# Power_Input_Board.net
KiCad netlist of a schematic drawn in EAGLE
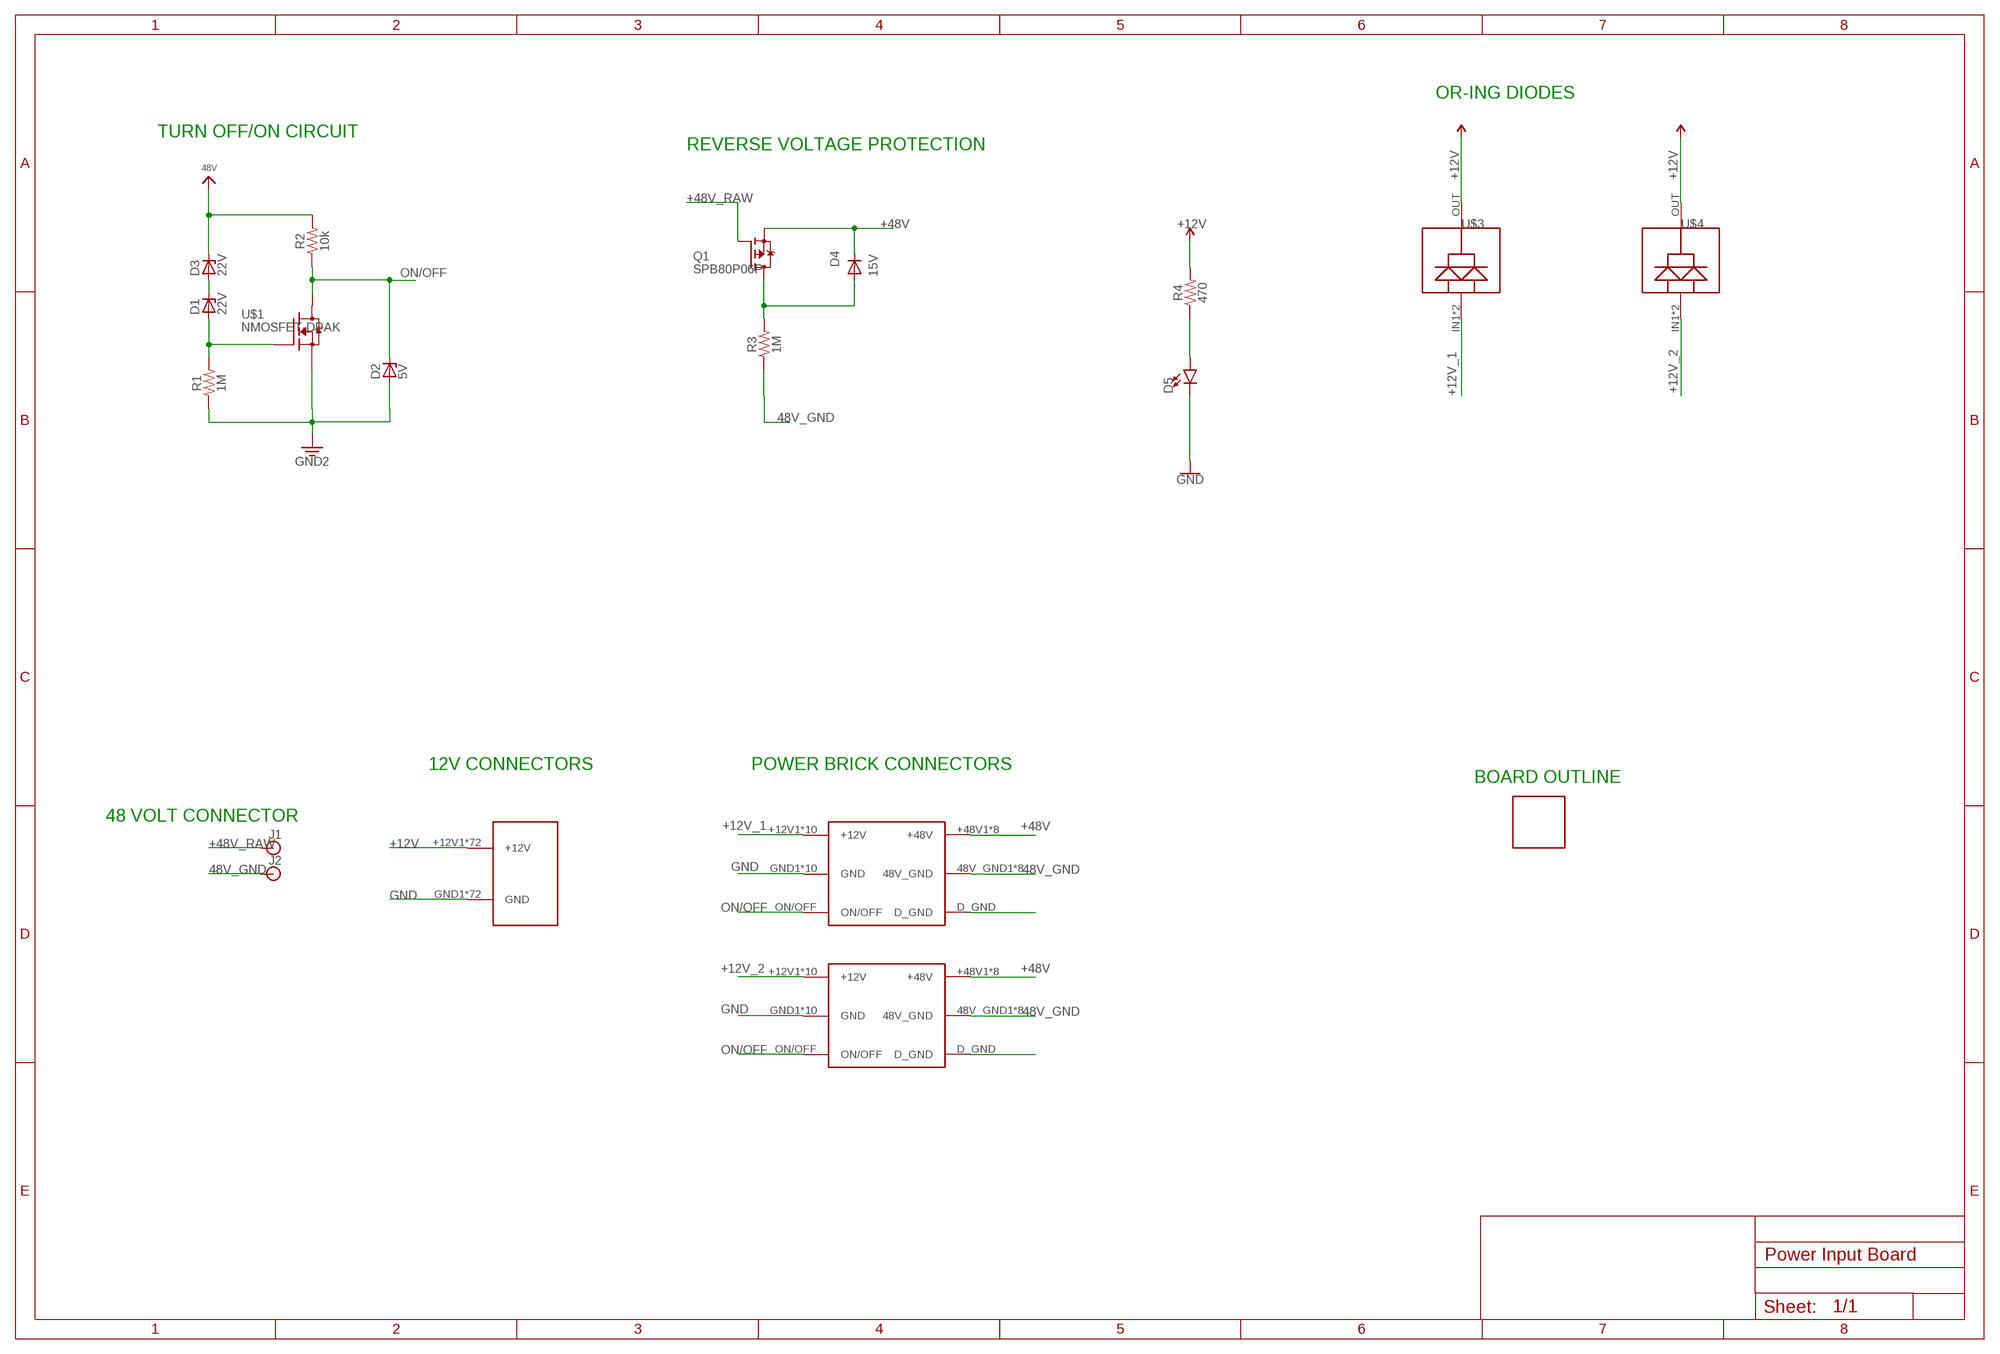
[diagram p0: schematic, sheet 1]

(export (version "E")
  (design (tool "Eeschema 10.0.6"))
  (components
    (comp (ref "D1")
      (value "22V")
      (footprint "eagle-import:SOT23")
      (libsource (lib "eagle-import") (part "ZENER-DIODESOT23"))
    )
    (comp (ref "D2")
      (value "5V")
      (footprint "eagle-import:SOT23")
      (libsource (lib "eagle-import") (part "ZENER-DIODESOT23"))
    )
    (comp (ref "D3")
      (value "22V")
      (footprint "eagle-import:SOT23")
      (libsource (lib "eagle-import") (part "ZENER-DIODESOT23"))
    )
    (comp (ref "D4")
      (value "15V")
      (footprint "eagle-import:SOD123")
      (libsource (lib "eagle-import") (part "DIODE-SOD123"))
    )
    (comp (ref "D5")
      (value "LED0603")
      (footprint "eagle-import:LED-0603")
      (libsource (lib "eagle-import") (part "LED0603"))
    )
    (comp (ref "J1")
      (value "BANANA_CONN")
      (footprint "eagle-import:BANANA_CONN")
      (libsource (lib "eagle-import") (part "BANANA_CONN"))
    )
    (comp (ref "J2")
      (value "BANANA_CONN")
      (footprint "eagle-import:BANANA_CONN")
      (libsource (lib "eagle-import") (part "BANANA_CONN"))
    )
    (comp (ref "Q1")
      (value "SPB80P06P")
      (footprint "eagle-import:TO263")
      (libsource (lib "eagle-import") (part "SPB80P06P"))
    )
    (comp (ref "R1")
      (value "1M")
      (footprint "eagle-import:0603")
      (fields (field (name "SPICEPREFIX") "R"))
      (libsource (lib "eagle-import") (part "RESISTOR0603"))
    )
    (comp (ref "R2")
      (value "10k")
      (footprint "eagle-import:0603")
      (fields (field (name "SPICEPREFIX") "R"))
      (libsource (lib "eagle-import") (part "RESISTOR0603"))
    )
    (comp (ref "R3")
      (value "1M")
      (footprint "eagle-import:0603")
      (fields (field (name "SPICEPREFIX") "R"))
      (libsource (lib "eagle-import") (part "RESISTOR0603"))
    )
    (comp (ref "R4")
      (value "470")
      (footprint "eagle-import:0603")
      (libsource (lib "eagle-import") (part "RESISTOR0603"))
    )
    (comp (ref "U$1")
      (value "NMOSFET-DPAK")
      (footprint "eagle-import:DPAK")
      (libsource (lib "eagle-import") (part "NMOSFET-DPAK"))
    )
    (comp (ref "U$2")
      (value "BOARDPDB")
      (footprint "eagle-import:PDB")
      (libsource (lib "eagle-import") (part "BOARDPDB"))
    )
    (comp (ref "U$3")
      (value "DIODE")
      (footprint "eagle-import:DIODE")
      (libsource (lib "eagle-import") (part "DIODE"))
    )
    (comp (ref "U$4")
      (value "DIODE")
      (footprint "eagle-import:DIODE")
      (libsource (lib "eagle-import") (part "DIODE"))
    )
    (comp (ref "U$5")
      (value "BRICK_TO_POWER_DIST_WHOLE")
      (footprint "eagle-import:BRICK_TO_POWER_DIST_WHOLE")
      (libsource (lib "eagle-import") (part "BRICK_TO_POWER_DIST_WHOLE"))
    )
    (comp (ref "U$6")
      (value "BRICK_TO_POWER_DIST_WHOLE")
      (footprint "eagle-import:BRICK_TO_POWER_DIST_WHOLE")
      (libsource (lib "eagle-import") (part "BRICK_TO_POWER_DIST_WHOLE"))
    )
    (comp (ref "U$7")
      (value "PDB_PCB_CONNEC")
      (footprint "eagle-import:PDB_PCB_2")
      (libsource (lib "eagle-import") (part "PDB_PCB_CONNEC"))
    )
  )
  (nets
    (net (code "1") (name "/+12V_1") (class "Default")
      (node (ref "U$3") (pin "IN1") (pinfunction "IN2_IN1") (pintype "bidirectional"))
      (node (ref "U$3") (pin "IN2") (pinfunction "IN2_IN2") (pintype "bidirectional"))
      (node (ref "U$5") (pin "+12V1") (pinfunction "+12V_+12V1") (pintype "bidirectional"))
      (node (ref "U$5") (pin "+12V10") (pinfunction "+12V_+12V10") (pintype "bidirectional"))
      (node (ref "U$5") (pin "+12V2") (pinfunction "+12V_+12V2") (pintype "bidirectional"))
      (node (ref "U$5") (pin "+12V3") (pinfunction "+12V_+12V3") (pintype "bidirectional"))
      (node (ref "U$5") (pin "+12V4") (pinfunction "+12V_+12V4") (pintype "bidirectional"))
      (node (ref "U$5") (pin "+12V5") (pinfunction "+12V_+12V5") (pintype "bidirectional"))
      (node (ref "U$5") (pin "+12V6") (pinfunction "+12V_+12V6") (pintype "bidirectional"))
      (node (ref "U$5") (pin "+12V7") (pinfunction "+12V_+12V7") (pintype "bidirectional"))
      (node (ref "U$5") (pin "+12V8") (pinfunction "+12V_+12V8") (pintype "bidirectional"))
      (node (ref "U$5") (pin "+12V9") (pinfunction "+12V_+12V9") (pintype "bidirectional"))
    )
    (net (code "2") (name "/+12V_2") (class "Default")
      (node (ref "U$4") (pin "IN1") (pinfunction "IN2_IN1") (pintype "bidirectional"))
      (node (ref "U$4") (pin "IN2") (pinfunction "IN2_IN2") (pintype "bidirectional"))
      (node (ref "U$6") (pin "+12V1") (pinfunction "+12V_+12V1") (pintype "bidirectional"))
      (node (ref "U$6") (pin "+12V10") (pinfunction "+12V_+12V10") (pintype "bidirectional"))
      (node (ref "U$6") (pin "+12V2") (pinfunction "+12V_+12V2") (pintype "bidirectional"))
      (node (ref "U$6") (pin "+12V3") (pinfunction "+12V_+12V3") (pintype "bidirectional"))
      (node (ref "U$6") (pin "+12V4") (pinfunction "+12V_+12V4") (pintype "bidirectional"))
      (node (ref "U$6") (pin "+12V5") (pinfunction "+12V_+12V5") (pintype "bidirectional"))
      (node (ref "U$6") (pin "+12V6") (pinfunction "+12V_+12V6") (pintype "bidirectional"))
      (node (ref "U$6") (pin "+12V7") (pinfunction "+12V_+12V7") (pintype "bidirectional"))
      (node (ref "U$6") (pin "+12V8") (pinfunction "+12V_+12V8") (pintype "bidirectional"))
      (node (ref "U$6") (pin "+12V9") (pinfunction "+12V_+12V9") (pintype "bidirectional"))
    )
    (net (code "3") (name "/+48V") (class "Default")
      (node (ref "D4") (pin "C") (pinfunction "C_C") (pintype "passive"))
      (node (ref "Q1") (pin "2") (pinfunction "S_2") (pintype "passive"))
      (node (ref "U$5") (pin "+48V1") (pinfunction "+48V_+48V1") (pintype "bidirectional"))
      (node (ref "U$5") (pin "+48V2") (pinfunction "+48V_+48V2") (pintype "bidirectional"))
      (node (ref "U$5") (pin "+48V3") (pinfunction "+48V_+48V3") (pintype "bidirectional"))
      (node (ref "U$5") (pin "+48V4") (pinfunction "+48V_+48V4") (pintype "bidirectional"))
      (node (ref "U$5") (pin "+48V5") (pinfunction "+48V_+48V5") (pintype "bidirectional"))
      (node (ref "U$5") (pin "+48V6") (pinfunction "+48V_+48V6") (pintype "bidirectional"))
      (node (ref "U$5") (pin "+48V7") (pinfunction "+48V_+48V7") (pintype "bidirectional"))
      (node (ref "U$5") (pin "+48V8") (pinfunction "+48V_+48V8") (pintype "bidirectional"))
      (node (ref "U$6") (pin "+48V1") (pinfunction "+48V_+48V1") (pintype "bidirectional"))
      (node (ref "U$6") (pin "+48V2") (pinfunction "+48V_+48V2") (pintype "bidirectional"))
      (node (ref "U$6") (pin "+48V3") (pinfunction "+48V_+48V3") (pintype "bidirectional"))
      (node (ref "U$6") (pin "+48V4") (pinfunction "+48V_+48V4") (pintype "bidirectional"))
      (node (ref "U$6") (pin "+48V5") (pinfunction "+48V_+48V5") (pintype "bidirectional"))
      (node (ref "U$6") (pin "+48V6") (pinfunction "+48V_+48V6") (pintype "bidirectional"))
      (node (ref "U$6") (pin "+48V7") (pinfunction "+48V_+48V7") (pintype "bidirectional"))
      (node (ref "U$6") (pin "+48V8") (pinfunction "+48V_+48V8") (pintype "bidirectional"))
    )
    (net (code "4") (name "/+48V_RAW") (class "Default")
      (node (ref "J1") (pin "P$1") (pinfunction "1_P$1") (pintype "passive"))
      (node (ref "Q1") (pin "1") (pinfunction "G_1") (pintype "passive"))
    )
    (net (code "5") (name "/48V_GND") (class "Default")
      (node (ref "J2") (pin "P$1") (pinfunction "1_P$1") (pintype "passive"))
      (node (ref "R3") (pin "1") (pinfunction "1_1") (pintype "passive"))
      (node (ref "U$5") (pin "48V_GND1") (pinfunction "48V_GND_48V_GND1") (pintype "bidirectional"))
      (node (ref "U$5") (pin "48V_GND2") (pinfunction "48V_GND_48V_GND2") (pintype "bidirectional"))
      (node (ref "U$5") (pin "48V_GND3") (pinfunction "48V_GND_48V_GND3") (pintype "bidirectional"))
      (node (ref "U$5") (pin "48V_GND4") (pinfunction "48V_GND_48V_GND4") (pintype "bidirectional"))
      (node (ref "U$5") (pin "48V_GND5") (pinfunction "48V_GND_48V_GND5") (pintype "bidirectional"))
      (node (ref "U$5") (pin "48V_GND6") (pinfunction "48V_GND_48V_GND6") (pintype "bidirectional"))
      (node (ref "U$5") (pin "48V_GND7") (pinfunction "48V_GND_48V_GND7") (pintype "bidirectional"))
      (node (ref "U$5") (pin "48V_GND8") (pinfunction "48V_GND_48V_GND8") (pintype "bidirectional"))
      (node (ref "U$6") (pin "48V_GND1") (pinfunction "48V_GND_48V_GND1") (pintype "bidirectional"))
      (node (ref "U$6") (pin "48V_GND2") (pinfunction "48V_GND_48V_GND2") (pintype "bidirectional"))
      (node (ref "U$6") (pin "48V_GND3") (pinfunction "48V_GND_48V_GND3") (pintype "bidirectional"))
      (node (ref "U$6") (pin "48V_GND4") (pinfunction "48V_GND_48V_GND4") (pintype "bidirectional"))
      (node (ref "U$6") (pin "48V_GND5") (pinfunction "48V_GND_48V_GND5") (pintype "bidirectional"))
      (node (ref "U$6") (pin "48V_GND6") (pinfunction "48V_GND_48V_GND6") (pintype "bidirectional"))
      (node (ref "U$6") (pin "48V_GND7") (pinfunction "48V_GND_48V_GND7") (pintype "bidirectional"))
      (node (ref "U$6") (pin "48V_GND8") (pinfunction "48V_GND_48V_GND8") (pintype "bidirectional"))
    )
    (net (code "6") (name "/ON{slash}OFF") (class "Default")
      (node (ref "D2") (pin "3") (pinfunction "C_3") (pintype "passive"))
      (node (ref "R2") (pin "1") (pinfunction "1_1") (pintype "passive"))
      (node (ref "U$1") (pin "4") (pinfunction "D1_4") (pintype "passive"))
      (node (ref "U$5") (pin "ON/OFF") (pinfunction "ON/OFF_ON/OFF") (pintype "bidirectional"))
      (node (ref "U$6") (pin "ON/OFF") (pinfunction "ON/OFF_ON/OFF") (pintype "bidirectional"))
    )
    (net (code "7") (name "48V") (class "Default")
      (node (ref "D3") (pin "3") (pinfunction "C_3") (pintype "passive"))
      (node (ref "R2") (pin "2") (pinfunction "2_2") (pintype "passive"))
    )
    (net (code "8") (name "GND") (class "Default")
      (node (ref "D5") (pin "C") (pinfunction "C_C") (pintype "passive"))
      (node (ref "U$5") (pin "GND1") (pinfunction "GND_GND1") (pintype "bidirectional"))
      (node (ref "U$5") (pin "GND10") (pinfunction "GND_GND10") (pintype "bidirectional"))
      (node (ref "U$5") (pin "GND2") (pinfunction "GND_GND2") (pintype "bidirectional"))
      (node (ref "U$5") (pin "GND3") (pinfunction "GND_GND3") (pintype "bidirectional"))
      (node (ref "U$5") (pin "GND4") (pinfunction "GND_GND4") (pintype "bidirectional"))
      (node (ref "U$5") (pin "GND5") (pinfunction "GND_GND5") (pintype "bidirectional"))
      (node (ref "U$5") (pin "GND6") (pinfunction "GND_GND6") (pintype "bidirectional"))
      (node (ref "U$5") (pin "GND7") (pinfunction "GND_GND7") (pintype "bidirectional"))
      (node (ref "U$5") (pin "GND8") (pinfunction "GND_GND8") (pintype "bidirectional"))
      (node (ref "U$5") (pin "GND9") (pinfunction "GND_GND9") (pintype "bidirectional"))
      (node (ref "U$6") (pin "GND1") (pinfunction "GND_GND1") (pintype "bidirectional"))
      (node (ref "U$6") (pin "GND10") (pinfunction "GND_GND10") (pintype "bidirectional"))
      (node (ref "U$6") (pin "GND2") (pinfunction "GND_GND2") (pintype "bidirectional"))
      (node (ref "U$6") (pin "GND3") (pinfunction "GND_GND3") (pintype "bidirectional"))
      (node (ref "U$6") (pin "GND4") (pinfunction "GND_GND4") (pintype "bidirectional"))
      (node (ref "U$6") (pin "GND5") (pinfunction "GND_GND5") (pintype "bidirectional"))
      (node (ref "U$6") (pin "GND6") (pinfunction "GND_GND6") (pintype "bidirectional"))
      (node (ref "U$6") (pin "GND7") (pinfunction "GND_GND7") (pintype "bidirectional"))
      (node (ref "U$6") (pin "GND8") (pinfunction "GND_GND8") (pintype "bidirectional"))
      (node (ref "U$6") (pin "GND9") (pinfunction "GND_GND9") (pintype "bidirectional"))
      (node (ref "U$7") (pin "GND1") (pinfunction "GND_GND1") (pintype "bidirectional"))
      (node (ref "U$7") (pin "GND10") (pinfunction "GND_GND10") (pintype "bidirectional"))
      (node (ref "U$7") (pin "GND11") (pinfunction "GND_GND11") (pintype "bidirectional"))
      (node (ref "U$7") (pin "GND12") (pinfunction "GND_GND12") (pintype "bidirectional"))
      (node (ref "U$7") (pin "GND13") (pinfunction "GND_GND13") (pintype "bidirectional"))
      (node (ref "U$7") (pin "GND14") (pinfunction "GND_GND14") (pintype "bidirectional"))
      (node (ref "U$7") (pin "GND15") (pinfunction "GND_GND15") (pintype "bidirectional"))
      (node (ref "U$7") (pin "GND16") (pinfunction "GND_GND16") (pintype "bidirectional"))
      (node (ref "U$7") (pin "GND17") (pinfunction "GND_GND17") (pintype "bidirectional"))
      (node (ref "U$7") (pin "GND18") (pinfunction "GND_GND18") (pintype "bidirectional"))
      (node (ref "U$7") (pin "GND19") (pinfunction "GND_GND19") (pintype "bidirectional"))
      (node (ref "U$7") (pin "GND2") (pinfunction "GND_GND2") (pintype "bidirectional"))
      (node (ref "U$7") (pin "GND20") (pinfunction "GND_GND20") (pintype "bidirectional"))
      (node (ref "U$7") (pin "GND21") (pinfunction "GND_GND21") (pintype "bidirectional"))
      (node (ref "U$7") (pin "GND22") (pinfunction "GND_GND22") (pintype "bidirectional"))
      (node (ref "U$7") (pin "GND23") (pinfunction "GND_GND23") (pintype "bidirectional"))
      (node (ref "U$7") (pin "GND24") (pinfunction "GND_GND24") (pintype "bidirectional"))
      (node (ref "U$7") (pin "GND25") (pinfunction "GND_GND25") (pintype "bidirectional"))
      (node (ref "U$7") (pin "GND26") (pinfunction "GND_GND26") (pintype "bidirectional"))
      (node (ref "U$7") (pin "GND27") (pinfunction "GND_GND27") (pintype "bidirectional"))
      (node (ref "U$7") (pin "GND28") (pinfunction "GND_GND28") (pintype "bidirectional"))
      (node (ref "U$7") (pin "GND29") (pinfunction "GND_GND29") (pintype "bidirectional"))
      (node (ref "U$7") (pin "GND3") (pinfunction "GND_GND3") (pintype "bidirectional"))
      (node (ref "U$7") (pin "GND30") (pinfunction "GND_GND30") (pintype "bidirectional"))
      (node (ref "U$7") (pin "GND31") (pinfunction "GND_GND31") (pintype "bidirectional"))
      (node (ref "U$7") (pin "GND32") (pinfunction "GND_GND32") (pintype "bidirectional"))
      (node (ref "U$7") (pin "GND33") (pinfunction "GND_GND33") (pintype "bidirectional"))
      (node (ref "U$7") (pin "GND34") (pinfunction "GND_GND34") (pintype "bidirectional"))
      (node (ref "U$7") (pin "GND35") (pinfunction "GND_GND35") (pintype "bidirectional"))
      (node (ref "U$7") (pin "GND36") (pinfunction "GND_GND36") (pintype "bidirectional"))
      (node (ref "U$7") (pin "GND37") (pinfunction "GND_GND37") (pintype "bidirectional"))
      (node (ref "U$7") (pin "GND38") (pinfunction "GND_GND38") (pintype "bidirectional"))
      (node (ref "U$7") (pin "GND39") (pinfunction "GND_GND39") (pintype "bidirectional"))
      (node (ref "U$7") (pin "GND4") (pinfunction "GND_GND4") (pintype "bidirectional"))
      (node (ref "U$7") (pin "GND40") (pinfunction "GND_GND40") (pintype "bidirectional"))
      (node (ref "U$7") (pin "GND41") (pinfunction "GND_GND41") (pintype "bidirectional"))
      (node (ref "U$7") (pin "GND42") (pinfunction "GND_GND42") (pintype "bidirectional"))
      (node (ref "U$7") (pin "GND43") (pinfunction "GND_GND43") (pintype "bidirectional"))
      (node (ref "U$7") (pin "GND44") (pinfunction "GND_GND44") (pintype "bidirectional"))
      (node (ref "U$7") (pin "GND45") (pinfunction "GND_GND45") (pintype "bidirectional"))
      (node (ref "U$7") (pin "GND46") (pinfunction "GND_GND46") (pintype "bidirectional"))
      (node (ref "U$7") (pin "GND47") (pinfunction "GND_GND47") (pintype "bidirectional"))
      (node (ref "U$7") (pin "GND48") (pinfunction "GND_GND48") (pintype "bidirectional"))
      (node (ref "U$7") (pin "GND49") (pinfunction "GND_GND49") (pintype "bidirectional"))
      (node (ref "U$7") (pin "GND5") (pinfunction "GND_GND5") (pintype "bidirectional"))
      (node (ref "U$7") (pin "GND50") (pinfunction "GND_GND50") (pintype "bidirectional"))
      (node (ref "U$7") (pin "GND51") (pinfunction "GND_GND51") (pintype "bidirectional"))
      (node (ref "U$7") (pin "GND52") (pinfunction "GND_GND52") (pintype "bidirectional"))
      (node (ref "U$7") (pin "GND53") (pinfunction "GND_GND53") (pintype "bidirectional"))
      (node (ref "U$7") (pin "GND54") (pinfunction "GND_GND54") (pintype "bidirectional"))
      (node (ref "U$7") (pin "GND55") (pinfunction "GND_GND55") (pintype "bidirectional"))
      (node (ref "U$7") (pin "GND56") (pinfunction "GND_GND56") (pintype "bidirectional"))
      (node (ref "U$7") (pin "GND57") (pinfunction "GND_GND57") (pintype "bidirectional"))
      (node (ref "U$7") (pin "GND58") (pinfunction "GND_GND58") (pintype "bidirectional"))
      (node (ref "U$7") (pin "GND59") (pinfunction "GND_GND59") (pintype "bidirectional"))
      (node (ref "U$7") (pin "GND6") (pinfunction "GND_GND6") (pintype "bidirectional"))
      (node (ref "U$7") (pin "GND60") (pinfunction "GND_GND60") (pintype "bidirectional"))
      (node (ref "U$7") (pin "GND61") (pinfunction "GND_GND61") (pintype "bidirectional"))
      (node (ref "U$7") (pin "GND62") (pinfunction "GND_GND62") (pintype "bidirectional"))
      (node (ref "U$7") (pin "GND63") (pinfunction "GND_GND63") (pintype "bidirectional"))
      (node (ref "U$7") (pin "GND64") (pinfunction "GND_GND64") (pintype "bidirectional"))
      (node (ref "U$7") (pin "GND65") (pinfunction "GND_GND65") (pintype "bidirectional"))
      (node (ref "U$7") (pin "GND66") (pinfunction "GND_GND66") (pintype "bidirectional"))
      (node (ref "U$7") (pin "GND67") (pinfunction "GND_GND67") (pintype "bidirectional"))
      (node (ref "U$7") (pin "GND68") (pinfunction "GND_GND68") (pintype "bidirectional"))
      (node (ref "U$7") (pin "GND69") (pinfunction "GND_GND69") (pintype "bidirectional"))
      (node (ref "U$7") (pin "GND7") (pinfunction "GND_GND7") (pintype "bidirectional"))
      (node (ref "U$7") (pin "GND70") (pinfunction "GND_GND70") (pintype "bidirectional"))
      (node (ref "U$7") (pin "GND71") (pinfunction "GND_GND71") (pintype "bidirectional"))
      (node (ref "U$7") (pin "GND72") (pinfunction "GND_GND72") (pintype "bidirectional"))
      (node (ref "U$7") (pin "GND8") (pinfunction "GND_GND8") (pintype "bidirectional"))
      (node (ref "U$7") (pin "GND9") (pinfunction "GND_GND9") (pintype "bidirectional"))
    )
    (net (code "9") (name "GND2") (class "Default")
      (node (ref "D2") (pin "1") (pinfunction "A_1") (pintype "passive"))
      (node (ref "R1") (pin "1") (pinfunction "1_1") (pintype "passive"))
      (node (ref "U$1") (pin "3") (pinfunction "S_3") (pintype "passive"))
    )
    (net (code "10") (name "Net-(D1-A)") (class "Default")
      (node (ref "D1") (pin "1") (pinfunction "A_1") (pintype "passive"))
      (node (ref "R1") (pin "2") (pinfunction "2_2") (pintype "passive"))
      (node (ref "U$1") (pin "1") (pinfunction "G_1") (pintype "passive"))
    )
    (net (code "11") (name "Net-(D1-C)") (class "Default")
      (node (ref "D1") (pin "3") (pinfunction "C_3") (pintype "passive"))
      (node (ref "D3") (pin "1") (pinfunction "A_1") (pintype "passive"))
    )
    (net (code "12") (name "Net-(D5-PadA)") (class "Default")
      (node (ref "D5") (pin "A") (pinfunction "A_A") (pintype "passive"))
      (node (ref "R4") (pin "1") (pinfunction "1_1") (pintype "passive"))
    )
    (net (code "13") (name "Net-(Q1-D)") (class "Default")
      (node (ref "D4") (pin "A") (pinfunction "A_A") (pintype "passive"))
      (node (ref "Q1") (pin "3") (pinfunction "D_3") (pintype "passive"))
      (node (ref "R3") (pin "2") (pinfunction "2_2") (pintype "passive"))
    )
    (net (code "14") (name "VCC") (class "Default")
      (node (ref "R4") (pin "2") (pinfunction "2_2") (pintype "passive"))
      (node (ref "U$3") (pin "OUT") (pinfunction "OUT_OUT") (pintype "bidirectional"))
      (node (ref "U$4") (pin "OUT") (pinfunction "OUT_OUT") (pintype "bidirectional"))
      (node (ref "U$7") (pin "+12V1") (pinfunction "+12V_+12V1") (pintype "bidirectional"))
      (node (ref "U$7") (pin "+12V10") (pinfunction "+12V_+12V10") (pintype "bidirectional"))
      (node (ref "U$7") (pin "+12V11") (pinfunction "+12V_+12V11") (pintype "bidirectional"))
      (node (ref "U$7") (pin "+12V12") (pinfunction "+12V_+12V12") (pintype "bidirectional"))
      (node (ref "U$7") (pin "+12V13") (pinfunction "+12V_+12V13") (pintype "bidirectional"))
      (node (ref "U$7") (pin "+12V14") (pinfunction "+12V_+12V14") (pintype "bidirectional"))
      (node (ref "U$7") (pin "+12V15") (pinfunction "+12V_+12V15") (pintype "bidirectional"))
      (node (ref "U$7") (pin "+12V16") (pinfunction "+12V_+12V16") (pintype "bidirectional"))
      (node (ref "U$7") (pin "+12V17") (pinfunction "+12V_+12V17") (pintype "bidirectional"))
      (node (ref "U$7") (pin "+12V18") (pinfunction "+12V_+12V18") (pintype "bidirectional"))
      (node (ref "U$7") (pin "+12V19") (pinfunction "+12V_+12V19") (pintype "bidirectional"))
      (node (ref "U$7") (pin "+12V2") (pinfunction "+12V_+12V2") (pintype "bidirectional"))
      (node (ref "U$7") (pin "+12V20") (pinfunction "+12V_+12V20") (pintype "bidirectional"))
      (node (ref "U$7") (pin "+12V21") (pinfunction "+12V_+12V21") (pintype "bidirectional"))
      (node (ref "U$7") (pin "+12V22") (pinfunction "+12V_+12V22") (pintype "bidirectional"))
      (node (ref "U$7") (pin "+12V23") (pinfunction "+12V_+12V23") (pintype "bidirectional"))
      (node (ref "U$7") (pin "+12V24") (pinfunction "+12V_+12V24") (pintype "bidirectional"))
      (node (ref "U$7") (pin "+12V25") (pinfunction "+12V_+12V25") (pintype "bidirectional"))
      (node (ref "U$7") (pin "+12V26") (pinfunction "+12V_+12V26") (pintype "bidirectional"))
      (node (ref "U$7") (pin "+12V27") (pinfunction "+12V_+12V27") (pintype "bidirectional"))
      (node (ref "U$7") (pin "+12V28") (pinfunction "+12V_+12V28") (pintype "bidirectional"))
      (node (ref "U$7") (pin "+12V29") (pinfunction "+12V_+12V29") (pintype "bidirectional"))
      (node (ref "U$7") (pin "+12V3") (pinfunction "+12V_+12V3") (pintype "bidirectional"))
      (node (ref "U$7") (pin "+12V30") (pinfunction "+12V_+12V30") (pintype "bidirectional"))
      (node (ref "U$7") (pin "+12V31") (pinfunction "+12V_+12V31") (pintype "bidirectional"))
      (node (ref "U$7") (pin "+12V32") (pinfunction "+12V_+12V32") (pintype "bidirectional"))
      (node (ref "U$7") (pin "+12V33") (pinfunction "+12V_+12V33") (pintype "bidirectional"))
      (node (ref "U$7") (pin "+12V34") (pinfunction "+12V_+12V34") (pintype "bidirectional"))
      (node (ref "U$7") (pin "+12V35") (pinfunction "+12V_+12V35") (pintype "bidirectional"))
      (node (ref "U$7") (pin "+12V36") (pinfunction "+12V_+12V36") (pintype "bidirectional"))
      (node (ref "U$7") (pin "+12V37") (pinfunction "+12V_+12V37") (pintype "bidirectional"))
      (node (ref "U$7") (pin "+12V38") (pinfunction "+12V_+12V38") (pintype "bidirectional"))
      (node (ref "U$7") (pin "+12V39") (pinfunction "+12V_+12V39") (pintype "bidirectional"))
      (node (ref "U$7") (pin "+12V4") (pinfunction "+12V_+12V4") (pintype "bidirectional"))
      (node (ref "U$7") (pin "+12V40") (pinfunction "+12V_+12V40") (pintype "bidirectional"))
      (node (ref "U$7") (pin "+12V41") (pinfunction "+12V_+12V41") (pintype "bidirectional"))
      (node (ref "U$7") (pin "+12V42") (pinfunction "+12V_+12V42") (pintype "bidirectional"))
      (node (ref "U$7") (pin "+12V43") (pinfunction "+12V_+12V43") (pintype "bidirectional"))
      (node (ref "U$7") (pin "+12V44") (pinfunction "+12V_+12V44") (pintype "bidirectional"))
      (node (ref "U$7") (pin "+12V45") (pinfunction "+12V_+12V45") (pintype "bidirectional"))
      (node (ref "U$7") (pin "+12V46") (pinfunction "+12V_+12V46") (pintype "bidirectional"))
      (node (ref "U$7") (pin "+12V47") (pinfunction "+12V_+12V47") (pintype "bidirectional"))
      (node (ref "U$7") (pin "+12V48") (pinfunction "+12V_+12V48") (pintype "bidirectional"))
      (node (ref "U$7") (pin "+12V49") (pinfunction "+12V_+12V49") (pintype "bidirectional"))
      (node (ref "U$7") (pin "+12V5") (pinfunction "+12V_+12V5") (pintype "bidirectional"))
      (node (ref "U$7") (pin "+12V50") (pinfunction "+12V_+12V50") (pintype "bidirectional"))
      (node (ref "U$7") (pin "+12V51") (pinfunction "+12V_+12V51") (pintype "bidirectional"))
      (node (ref "U$7") (pin "+12V52") (pinfunction "+12V_+12V52") (pintype "bidirectional"))
      (node (ref "U$7") (pin "+12V53") (pinfunction "+12V_+12V53") (pintype "bidirectional"))
      (node (ref "U$7") (pin "+12V54") (pinfunction "+12V_+12V54") (pintype "bidirectional"))
      (node (ref "U$7") (pin "+12V55") (pinfunction "+12V_+12V55") (pintype "bidirectional"))
      (node (ref "U$7") (pin "+12V56") (pinfunction "+12V_+12V56") (pintype "bidirectional"))
      (node (ref "U$7") (pin "+12V57") (pinfunction "+12V_+12V57") (pintype "bidirectional"))
      (node (ref "U$7") (pin "+12V58") (pinfunction "+12V_+12V58") (pintype "bidirectional"))
      (node (ref "U$7") (pin "+12V59") (pinfunction "+12V_+12V59") (pintype "bidirectional"))
      (node (ref "U$7") (pin "+12V6") (pinfunction "+12V_+12V6") (pintype "bidirectional"))
      (node (ref "U$7") (pin "+12V60") (pinfunction "+12V_+12V60") (pintype "bidirectional"))
      (node (ref "U$7") (pin "+12V61") (pinfunction "+12V_+12V61") (pintype "bidirectional"))
      (node (ref "U$7") (pin "+12V62") (pinfunction "+12V_+12V62") (pintype "bidirectional"))
      (node (ref "U$7") (pin "+12V63") (pinfunction "+12V_+12V63") (pintype "bidirectional"))
      (node (ref "U$7") (pin "+12V64") (pinfunction "+12V_+12V64") (pintype "bidirectional"))
      (node (ref "U$7") (pin "+12V65") (pinfunction "+12V_+12V65") (pintype "bidirectional"))
      (node (ref "U$7") (pin "+12V66") (pinfunction "+12V_+12V66") (pintype "bidirectional"))
      (node (ref "U$7") (pin "+12V67") (pinfunction "+12V_+12V67") (pintype "bidirectional"))
      (node (ref "U$7") (pin "+12V68") (pinfunction "+12V_+12V68") (pintype "bidirectional"))
      (node (ref "U$7") (pin "+12V69") (pinfunction "+12V_+12V69") (pintype "bidirectional"))
      (node (ref "U$7") (pin "+12V7") (pinfunction "+12V_+12V7") (pintype "bidirectional"))
      (node (ref "U$7") (pin "+12V70") (pinfunction "+12V_+12V70") (pintype "bidirectional"))
      (node (ref "U$7") (pin "+12V71") (pinfunction "+12V_+12V71") (pintype "bidirectional"))
      (node (ref "U$7") (pin "+12V72") (pinfunction "+12V_+12V72") (pintype "bidirectional"))
      (node (ref "U$7") (pin "+12V8") (pinfunction "+12V_+12V8") (pintype "bidirectional"))
      (node (ref "U$7") (pin "+12V9") (pinfunction "+12V_+12V9") (pintype "bidirectional"))
    )
    (net (code "15") (name "unconnected-(U$5-PadD_GND)") (class "Default")
      (node (ref "U$5") (pin "D_GND") (pinfunction "D_GND_D_GND") (pintype "bidirectional"))
    )
    (net (code "16") (name "unconnected-(U$6-PadD_GND)") (class "Default")
      (node (ref "U$6") (pin "D_GND") (pinfunction "D_GND_D_GND") (pintype "bidirectional"))
    )
  )
)
